# SCH.net
KiCad netlist of a schematic drawn in EasyEDA
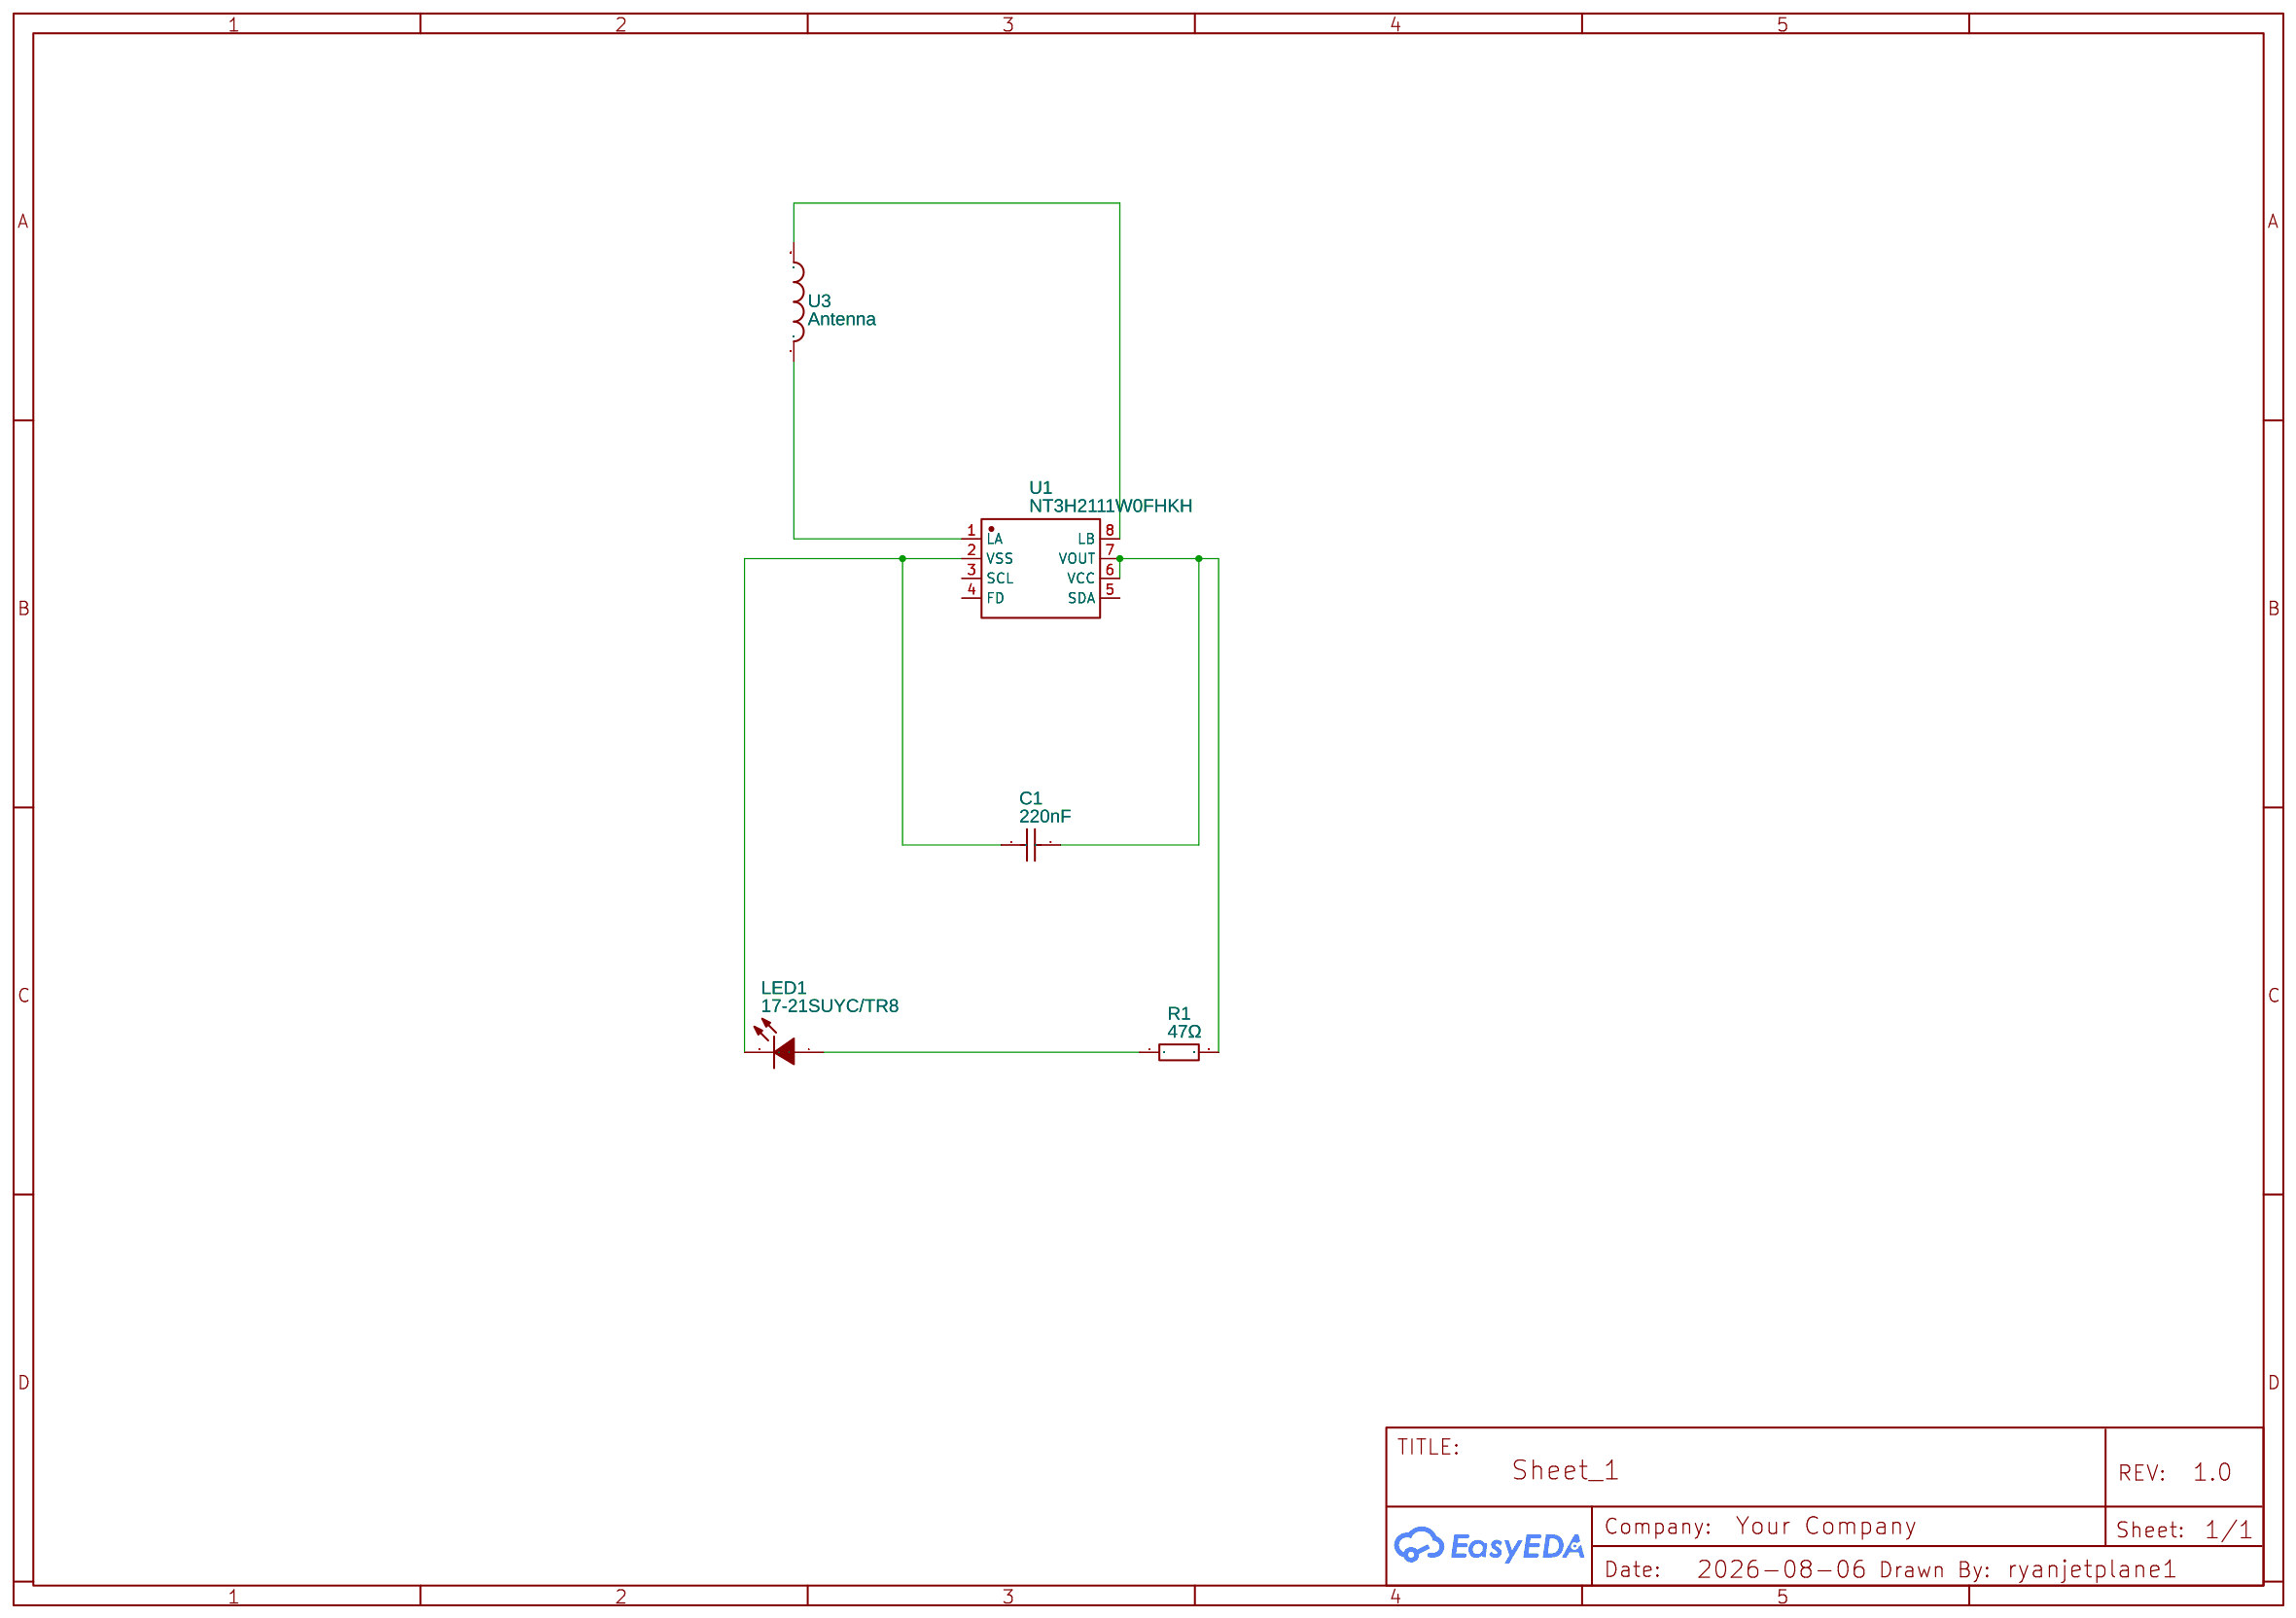
[diagram p0: schematic sheet]

(export (version "E")
  (design (tool "Eeschema 10.0.6"))
  (components
    (comp (ref "C1")
      (value "220nF")
      (fields
        (field (name "Manufacturer Part") "CL10B224KA8NNNC")
        (field (name "Manufacturer") "SAMSUNG(三星)")
      )
      (libsource (lib "") (part "CL10B224KA8NNNC"))
    )
    (comp (ref "LED1")
      (value "17-21SUYC/TR8")
      (fields (field (name "Manufacturer Part") "KT-0805黄灯") (field (name "Manufacturer") "KENTO"))
      (libsource (lib "") (part "17-21SUYC/TR8"))
    )
    (comp (ref "R1")
      (value "47Ω")
      (fields
        (field (name "Manufacturer Part") "0603WAF470JT5E")
        (field (name "Manufacturer") "UNI-ROYAL(厚声)")
      )
      (libsource (lib "") (part "0603WAF470JT5E"))
    )
    (comp (ref "U1")
      (value "NT3H2111W0FHKH")
      (fields (field (name "Manufacturer") "NXP(恩智浦)"))
      (libsource (lib "") (part "NT3H2111W0FHKH"))
    )
    (comp (ref "U3") (value "Antenna") (libsource (lib "") (part "Antenna")))
  )
  (nets
    (net (code "1") (name "Net-(LED1-+)") (class "Default")
      (node (ref "LED1") (pin "1") (pinfunction "+_1") (pintype "unspecified"))
      (node (ref "R1") (pin "1") (pinfunction "1_1") (pintype "input"))
    )
    (net (code "2") (name "Net-(LED1--)") (class "Default")
      (node (ref "C1") (pin "1") (pinfunction "1_1") (pintype "input"))
      (node (ref "LED1") (pin "2") (pinfunction "-_2") (pintype "unspecified"))
      (node (ref "U1") (pin "2") (pinfunction "VSS_2") (pintype "unspecified"))
    )
    (net (code "3") (name "Net-(U1-LA)") (class "Default")
      (node (ref "U1") (pin "1") (pinfunction "LA_1") (pintype "unspecified"))
      (node (ref "U3") (pin "P$1") (pinfunction "P$1_P$1") (pintype "unspecified"))
    )
    (net (code "4") (name "Net-(U1-LB)") (class "Default")
      (node (ref "U1") (pin "8") (pinfunction "LB_8") (pintype "unspecified"))
      (node (ref "U3") (pin "P$2") (pinfunction "P$2_P$2") (pintype "unspecified"))
    )
    (net (code "5") (name "Net-(U1-VCC)") (class "Default")
      (node (ref "C1") (pin "2") (pinfunction "2_2") (pintype "input"))
      (node (ref "R1") (pin "2") (pinfunction "2_2") (pintype "input"))
      (node (ref "U1") (pin "6") (pinfunction "VCC_6") (pintype "unspecified"))
      (node (ref "U1") (pin "7") (pinfunction "VOUT_7") (pintype "unspecified"))
    )
    (net (code "6") (name "unconnected-(U1-FD-Pad4)") (class "Default")
      (node (ref "U1") (pin "4") (pinfunction "FD_4") (pintype "unspecified"))
    )
    (net (code "7") (name "unconnected-(U1-SCL-Pad3)") (class "Default")
      (node (ref "U1") (pin "3") (pinfunction "SCL_3") (pintype "unspecified"))
    )
    (net (code "8") (name "unconnected-(U1-SDA-Pad5)") (class "Default")
      (node (ref "U1") (pin "5") (pinfunction "SDA_5") (pintype "unspecified"))
    )
  )
)
